# Connector-USB.net
KiCad netlist of a schematic drawn in Altium Designer
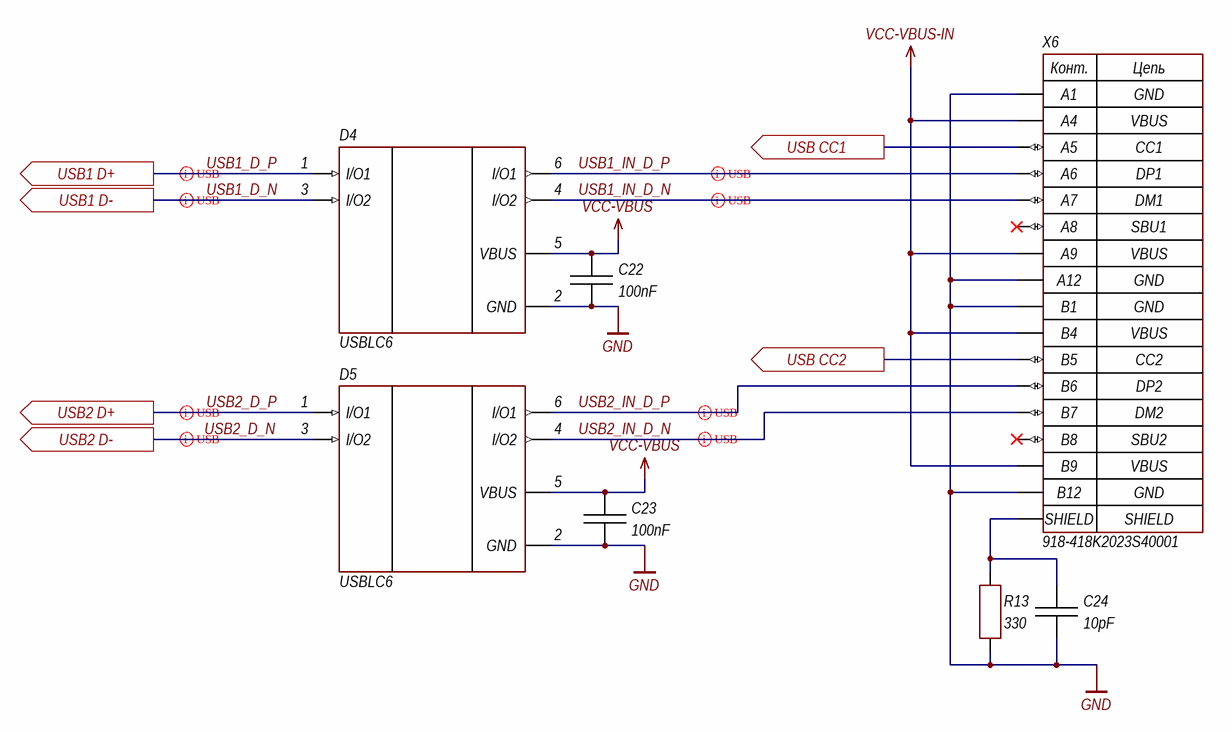
[diagram p0: Connector-USB.SchDoc]

(export (version "E")
  (design (tool "Eeschema 10.0.6"))
  (components
    (comp (ref "C22") (value "100nF") (footprint "CH0402C") (libsource (lib "Discrete") (part "Capacitor")))
    (comp (ref "C23") (value "100nF") (footprint "CH0402C") (libsource (lib "Discrete") (part "Capacitor")))
    (comp (ref "C24") (value "10pF") (footprint "CH0402C") (libsource (lib "Discrete") (part "Capacitor")))
    (comp (ref "D4")
      (value "USBLC6")
      (footprint "SOT666")
      (description "USB protection")
      (fields (field (name "MANUFACTURER") "STMicroelectronics"))
      (libsource (lib "Analog") (part "USBLC6"))
    )
    (comp (ref "D5")
      (value "USBLC6")
      (footprint "SOT666")
      (description "USB protection")
      (fields (field (name "MANUFACTURER") "STMicroelectronics"))
      (libsource (lib "Analog") (part "USBLC6"))
    )
    (comp (ref "R13") (value "330") (footprint "CH0402R") (libsource (lib "Discrete") (part "Resistor")))
    (comp (ref "X6")
      (value "918-418K2023S40001")
      (footprint "CON:  918-418K2023S40001")
      (description "USB-C 2.0 12(16)-pin")
      (libsource (lib "Connectors") (part "USB-C-12(16)"))
    )
  )
  (nets
    (net (code "1") (name "/USB CC1") (class "Default")
      (node (ref "X6") (pin "A5") (pinfunction "A5_A5") (pintype "bidirectional"))
    )
    (net (code "2") (name "/USB CC2") (class "Default")
      (node (ref "X6") (pin "B5") (pinfunction "B5_B5") (pintype "bidirectional"))
    )
    (net (code "3") (name "/USB1_D_N") (class "Default")
      (node (ref "D4") (pin "3") (pinfunction "I/O2_3") (pintype "input"))
    )
    (net (code "4") (name "/USB1_D_P") (class "Default")
      (node (ref "D4") (pin "1") (pinfunction "I/O1_1") (pintype "input"))
    )
    (net (code "5") (name "/USB1_IN_D_N") (class "Default")
      (node (ref "D4") (pin "4") (pinfunction "I/O2_4") (pintype "output"))
      (node (ref "X6") (pin "A7") (pinfunction "A7_A7") (pintype "bidirectional"))
    )
    (net (code "6") (name "/USB1_IN_D_P") (class "Default")
      (node (ref "D4") (pin "6") (pinfunction "I/O1_6") (pintype "output"))
      (node (ref "X6") (pin "A6") (pinfunction "A6_A6") (pintype "bidirectional"))
    )
    (net (code "7") (name "/USB2_D_N") (class "Default")
      (node (ref "D5") (pin "3") (pinfunction "I/O2_3") (pintype "input"))
    )
    (net (code "8") (name "/USB2_D_P") (class "Default")
      (node (ref "D5") (pin "1") (pinfunction "I/O1_1") (pintype "input"))
    )
    (net (code "9") (name "/USB2_IN_D_N") (class "Default")
      (node (ref "D5") (pin "4") (pinfunction "I/O2_4") (pintype "output"))
      (node (ref "X6") (pin "B7") (pinfunction "B7_B7") (pintype "bidirectional"))
    )
    (net (code "10") (name "/USB2_IN_D_P") (class "Default")
      (node (ref "D5") (pin "6") (pinfunction "I/O1_6") (pintype "output"))
      (node (ref "X6") (pin "B6") (pinfunction "B6_B6") (pintype "bidirectional"))
    )
    (net (code "11") (name "GND") (class "Default")
      (node (ref "C22") (pin "1") (pinfunction "1_1") (pintype "passive"))
      (node (ref "C23") (pin "1") (pinfunction "1_1") (pintype "passive"))
      (node (ref "C24") (pin "1") (pinfunction "1_1") (pintype "passive"))
      (node (ref "D4") (pin "2") (pinfunction "GND_2") (pintype "passive"))
      (node (ref "D5") (pin "2") (pinfunction "GND_2") (pintype "passive"))
      (node (ref "R13") (pin "1") (pinfunction "1_1") (pintype "passive"))
      (node (ref "X6") (pin "A1") (pinfunction "A1_A1") (pintype "power_in"))
      (node (ref "X6") (pin "A12") (pinfunction "A12_A12") (pintype "power_in"))
      (node (ref "X6") (pin "B1") (pinfunction "B1_B1") (pintype "power_in"))
      (node (ref "X6") (pin "B12") (pinfunction "B12_B12") (pintype "power_in"))
    )
    (net (code "12") (name "Net-(C24-Pad2)") (class "Default")
      (node (ref "C24") (pin "2") (pinfunction "2_2") (pintype "passive"))
      (node (ref "R13") (pin "2") (pinfunction "2_2") (pintype "passive"))
      (node (ref "X6") (pin "SHIELD") (pinfunction "SHIELD_SHIELD") (pintype "passive"))
    )
    (net (code "13") (name "VCC-VBUS") (class "Default")
      (node (ref "C22") (pin "2") (pinfunction "2_2") (pintype "passive"))
      (node (ref "C23") (pin "2") (pinfunction "2_2") (pintype "passive"))
      (node (ref "D4") (pin "5") (pinfunction "VBUS_5") (pintype "passive"))
      (node (ref "D5") (pin "5") (pinfunction "VBUS_5") (pintype "passive"))
    )
    (net (code "14") (name "VCC-VBUS-IN") (class "Default")
      (node (ref "X6") (pin "A4") (pinfunction "A4_A4") (pintype "power_in"))
      (node (ref "X6") (pin "A9") (pinfunction "A9_A9") (pintype "power_in"))
      (node (ref "X6") (pin "B4") (pinfunction "B4_B4") (pintype "passive"))
      (node (ref "X6") (pin "B9") (pinfunction "B9_B9") (pintype "power_in"))
    )
    (net (code "15") (name "unconnected-(X6-PadA8)") (class "Default")
      (node (ref "X6") (pin "A8") (pinfunction "A8_A8") (pintype "bidirectional+no_connect"))
    )
    (net (code "16") (name "unconnected-(X6-PadB8)") (class "Default")
      (node (ref "X6") (pin "B8") (pinfunction "B8_B8") (pintype "bidirectional+no_connect"))
    )
  )
)
